# 501_RPiCM4.net
KiCad netlist of a schematic drawn in Altium Designer
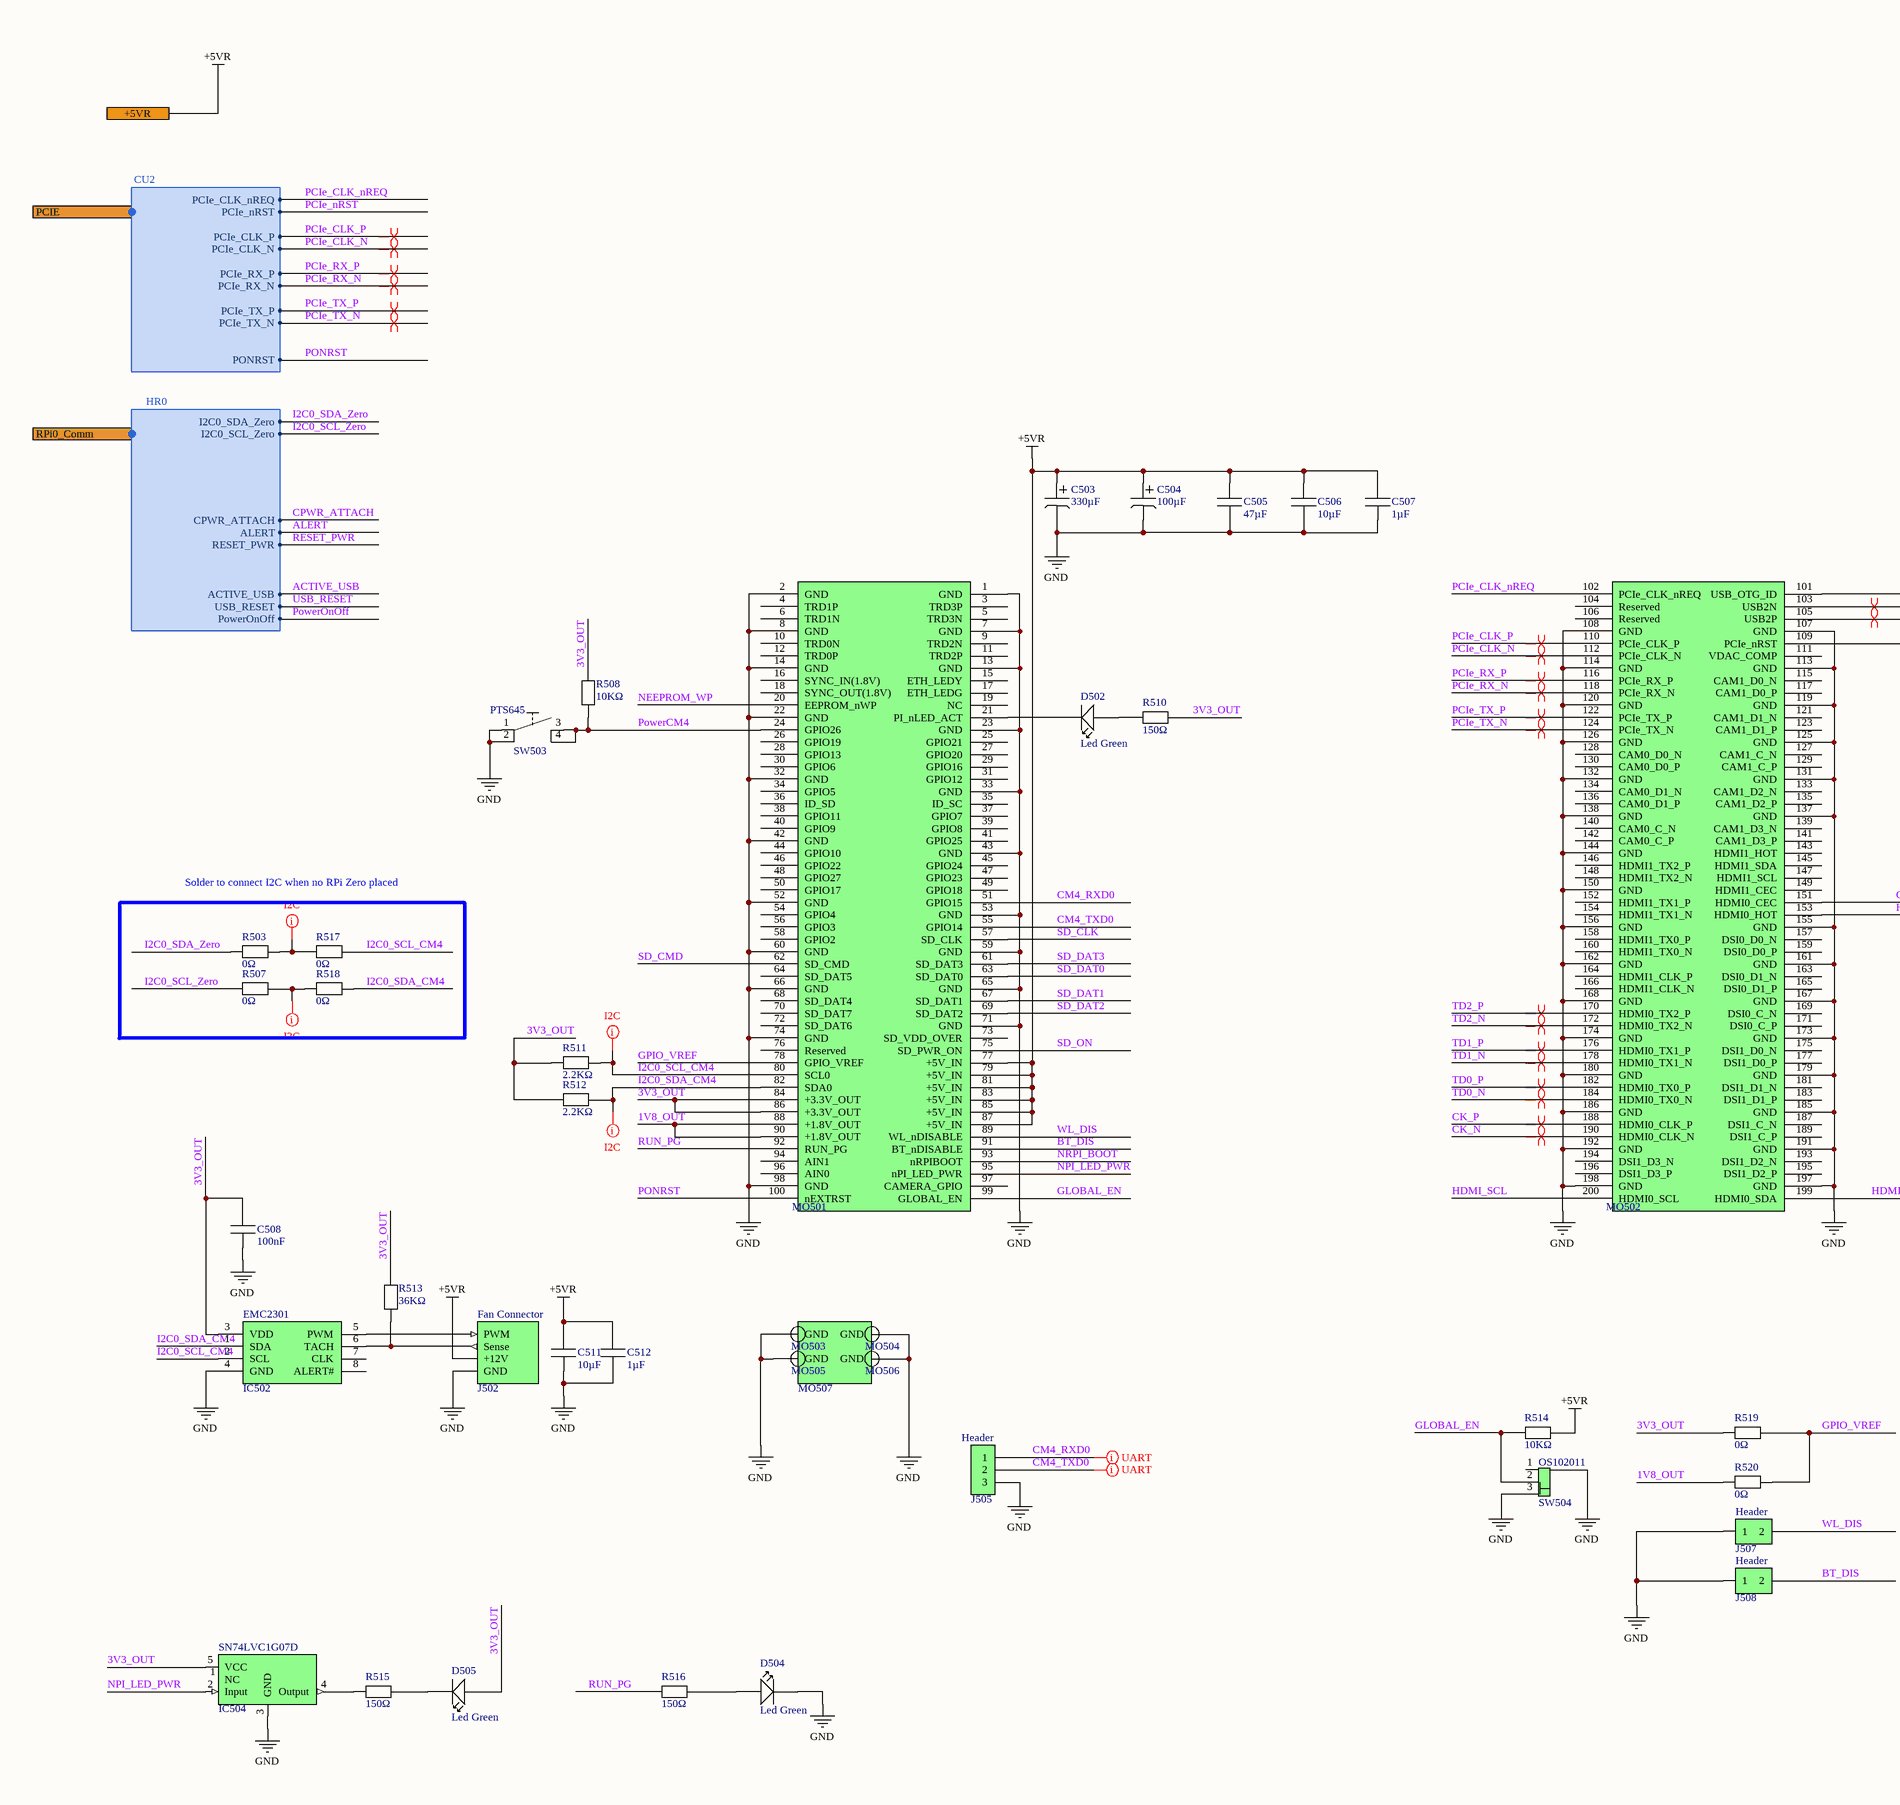
[diagram p0: 501_RPiCM4.SchDoc, left]
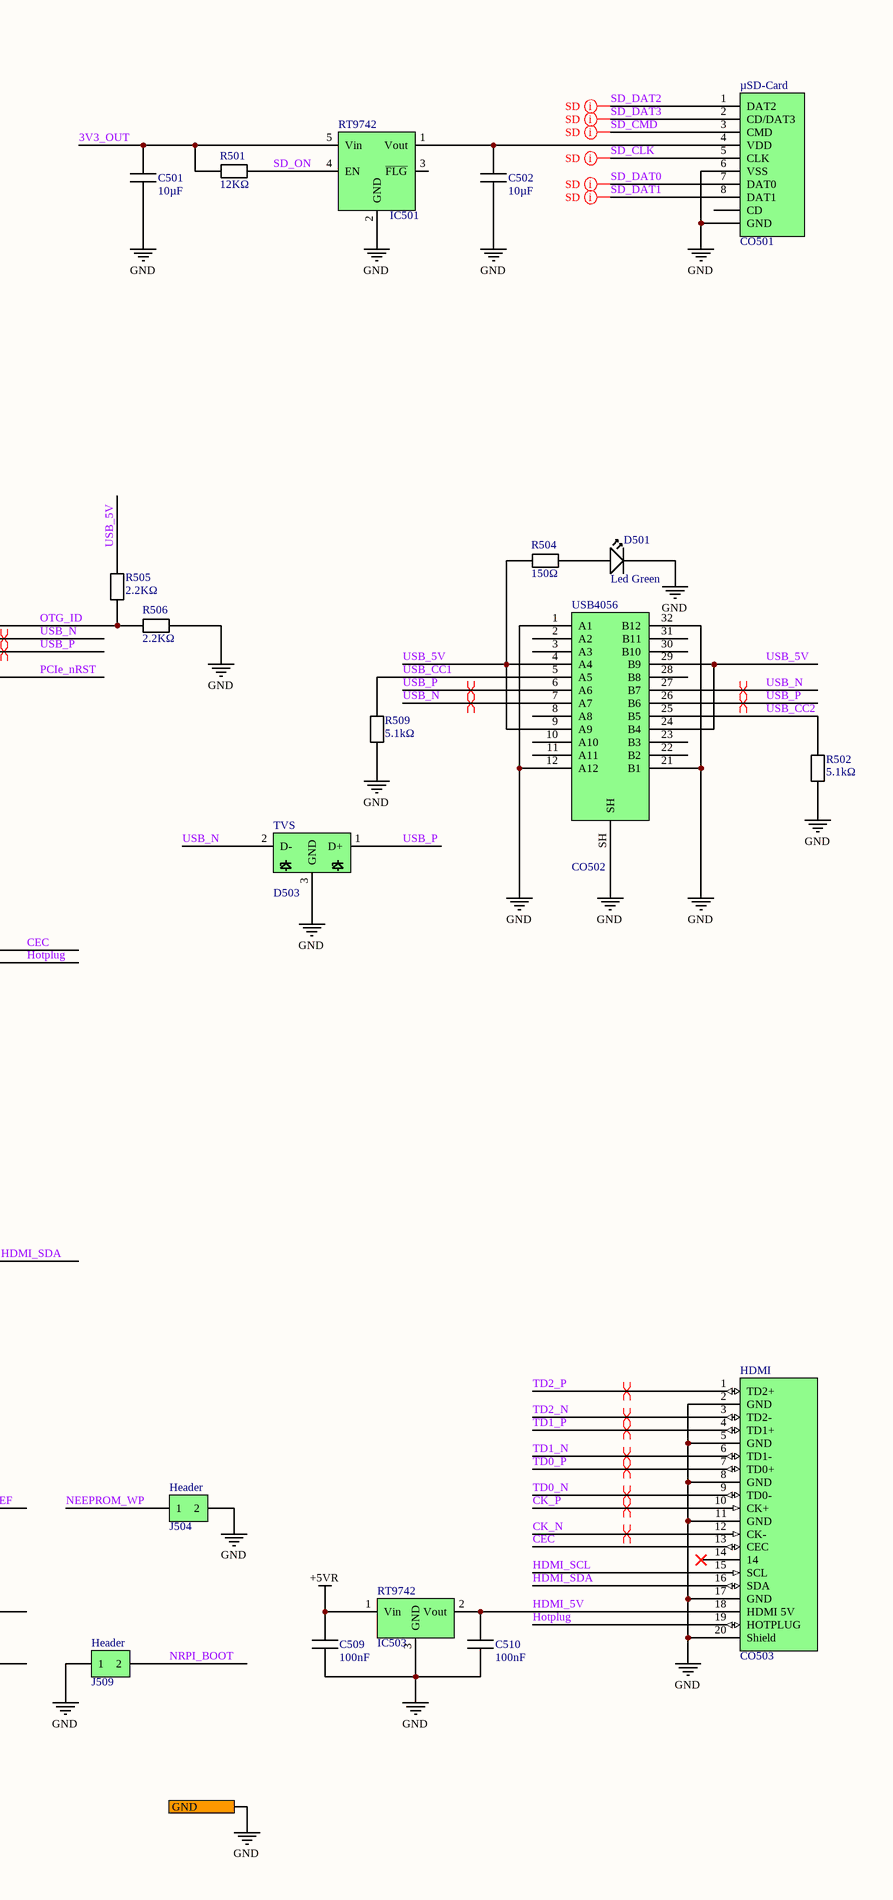
[diagram p1: 501_RPiCM4.SchDoc, right]

(export (version "E")
  (design (tool "Eeschema 10.0.6"))
  (components
    (comp (ref "C501")
      (value "10µF")
      (footprint "C0603")
      (description "10µF 16V 20% X5R")
      (fields
        (field (name "REFVAL") "10µF")
        (field (name "PART NUMBER") "CA0008")
        (field (name "MANFACTPART") "GRM188R61C106MAALD")
      )
      (libsource (lib "GTS_Database") (part "C"))
    )
    (comp (ref "C502")
      (value "10µF")
      (footprint "C0603")
      (description "10µF 16V 20% X5R")
      (fields
        (field (name "REFVAL") "10µF")
        (field (name "PART NUMBER") "CA0008")
        (field (name "MANFACTPART") "GRM188R61C106MAALD")
      )
      (libsource (lib "GTS_Database") (part "C"))
    )
    (comp (ref "C503")
      (value "330µF")
      (footprint "EC_E7")
      (description "330µF 16V 20% 16mΩ 4100mA")
      (fields
        (field (name "REFVAL") "330µF")
        (field (name "PART NUMBER") "CA0012")
        (field (name "MANFACTPART") "16SVPG330MX")
      )
      (libsource (lib "GTS_Database") (part "C+"))
    )
    (comp (ref "C504")
      (value "100µF")
      (footprint "EC_B6")
      (description "100µF 16V 20% 15mΩ 4000mA")
      (fields
        (field (name "REFVAL") "100µF")
        (field (name "PART NUMBER") "CA0011")
        (field (name "MANFACTPART") "16SVPG100M")
      )
      (libsource (lib "GTS_Database") (part "C+"))
    )
    (comp (ref "C505")
      (value "47µF")
      (footprint "C1210")
      (description "47µF 16V 20% X5R")
      (fields
        (field (name "REFVAL") "47µF")
        (field (name "PART NUMBER") "CA0007")
        (field (name "MANFACTPART") "EMK325ABJ476MM8P")
      )
      (libsource (lib "GTS_Database") (part "C"))
    )
    (comp (ref "C506")
      (value "10µF")
      (footprint "C0603")
      (description "10µF 16V 20% X5R")
      (fields
        (field (name "REFVAL") "10µF")
        (field (name "PART NUMBER") "CA0008")
        (field (name "MANFACTPART") "GRM188R61C106MAALD")
      )
      (libsource (lib "GTS_Database") (part "C"))
    )
    (comp (ref "C507")
      (value "1µF")
      (footprint "C0603")
      (description "1µF 16V 10% X5R")
      (fields
        (field (name "REFVAL") "1µF")
        (field (name "PART NUMBER") "CA0003")
        (field (name "MANFACTPART") "C1608X5R1C105K080AA")
      )
      (libsource (lib "GTS_Database") (part "C"))
    )
    (comp (ref "C508")
      (value "100nF")
      (footprint "C0402")
      (description "100nF 16V 10% X7R")
      (fields
        (field (name "REFVAL") "100nF")
        (field (name "PART NUMBER") "CA0010")
        (field (name "MANFACTPART") "GCM155R71C104KA55D")
      )
      (libsource (lib "GTS_Database") (part "C"))
    )
    (comp (ref "C509")
      (value "100nF")
      (footprint "C0402")
      (description "100nF 16V 10% X7R")
      (fields
        (field (name "REFVAL") "100nF")
        (field (name "PART NUMBER") "CA0010")
        (field (name "MANFACTPART") "GCM155R71C104KA55D")
      )
      (libsource (lib "GTS_Database") (part "C"))
    )
    (comp (ref "C510")
      (value "100nF")
      (footprint "C0402")
      (description "100nF 16V 10% X7R")
      (fields
        (field (name "REFVAL") "100nF")
        (field (name "PART NUMBER") "CA0010")
        (field (name "MANFACTPART") "GCM155R71C104KA55D")
      )
      (libsource (lib "GTS_Database") (part "C"))
    )
    (comp (ref "C511")
      (value "10µF")
      (footprint "C0603")
      (description "10µF 16V 20% X5R")
      (fields
        (field (name "REFVAL") "10µF")
        (field (name "PART NUMBER") "CA0008")
        (field (name "MANFACTPART") "GRM188R61C106MAALD")
      )
      (libsource (lib "GTS_Database") (part "C"))
    )
    (comp (ref "C512")
      (value "1µF")
      (footprint "C0603")
      (description "1µF 16V 10% X5R")
      (fields
        (field (name "REFVAL") "1µF")
        (field (name "PART NUMBER") "CA0003")
        (field (name "MANFACTPART") "C1608X5R1C105K080AA")
      )
      (libsource (lib "GTS_Database") (part "C"))
    )
    (comp (ref "CO501")
      (value "µSD-Card")
      (footprint "693071030811")
      (description "µSD-Card holder")
      (fields
        (field (name "REFVAL") "µSD-Card")
        (field (name "PART NUMBER") "CO0027")
        (field (name "MANFACTPART") "693071030811")
      )
      (libsource (lib "GTS_Database") (part "MICROSD-CARD"))
    )
    (comp (ref "CO502")
      (value "USB4056")
      (footprint "USB4056-03-A")
      (description "USB C connector Receptacle Horizontal")
      (fields
        (field (name "REFVAL") "USB4056")
        (field (name "PART NUMBER") "CO0030")
        (field (name "MANFACTPART") "USB4056-03-A")
      )
      (libsource (lib "GTS_Database") (part "USB-CC"))
    )
    (comp (ref "CO503")
      (value "HDMI")
      (footprint "HDMI")
      (fields
        (field (name "REFVAL") "HDMI")
        (field (name "PART NUMBER") "CO0007")
        (field (name "MANFACTPART") "10029449")
      )
      (libsource (lib "GTS_Database") (part "HDMI"))
    )
    (comp (ref "D501")
      (value "Led Green")
      (footprint "Led0805")
      (fields
        (field (name "REFVAL") "Led Green")
        (field (name "PART NUMBER") "DI0001")
        (field (name "MANFACTPART") "KP-2012CGCK")
      )
      (libsource (lib "GTS_Database") (part "Led"))
    )
    (comp (ref "D502")
      (value "Led Green")
      (footprint "Led0805")
      (fields
        (field (name "REFVAL") "Led Green")
        (field (name "PART NUMBER") "DI0001")
        (field (name "MANFACTPART") "KP-2012CGCK")
      )
      (libsource (lib "GTS_Database") (part "Led"))
    )
    (comp (ref "D503")
      (value "TVS")
      (footprint "SOT-3")
      (description "USB 2 TVS Diode")
      (fields
        (field (name "REFVAL") "TVS")
        (field (name "PART NUMBER") "DI0002")
        (field (name "MANFACTPART") "TPD2EUSB30DRTR")
      )
      (libsource (lib "GTS_Database") (part "USB2TVS"))
    )
    (comp (ref "D504")
      (value "Led Green")
      (footprint "Led0805")
      (fields
        (field (name "REFVAL") "Led Green")
        (field (name "PART NUMBER") "DI0001")
        (field (name "MANFACTPART") "KP-2012CGCK")
      )
      (libsource (lib "GTS_Database") (part "Led"))
    )
    (comp (ref "D505")
      (value "Led Green")
      (footprint "Led0805")
      (fields
        (field (name "REFVAL") "Led Green")
        (field (name "PART NUMBER") "DI0001")
        (field (name "MANFACTPART") "KP-2012CGCK")
      )
      (libsource (lib "GTS_Database") (part "Led"))
    )
    (comp (ref "IC501")
      (value "RT9742")
      (footprint "SOT-23-5")
      (description "RT9742 High side power switch")
      (fields
        (field (name "REFVAL") "RT9742")
        (field (name "PART NUMBER") "IC0029")
        (field (name "MANFACTPART") "RT9742GGJ5")
      )
      (libsource (lib "GTS_Database") (part "RT9742_EN"))
    )
    (comp (ref "IC502")
      (value "EMC2301")
      (footprint "MSOP-8_3X3")
      (description "Board Mount Temperature Sensors Single RPB-Based PWM Fan Speed CNTRL")
      (fields
        (field (name "REFVAL") "EMC2301")
        (field (name "PART NUMBER") "IC0054")
        (field (name "MANFACTPART") "EMC2301-1-ACZL-TR")
      )
      (libsource (lib "GTS_Database") (part "EMC2301"))
    )
    (comp (ref "IC503")
      (value "RT9742")
      (footprint "SOT-23")
      (description "RT9742SNGV")
      (fields (field (name "REFVAL") "RT9742") (field (name "PART NUMBER") "IC0011"))
      (libsource (lib "GTS_Database") (part "RT9742"))
    )
    (comp (ref "IC504")
      (value "SN74LVC1G07D")
      (footprint "SOT-23-5")
      (description "Buffer IC")
      (fields
        (field (name "REFVAL") "SN74LVC1G07D")
        (field (name "PART NUMBER") "IC0009")
        (field (name "MANFACTPART") "SN74LVC1G07DBVT")
      )
      (libsource (lib "GTS_Database") (part "SN74LVC1G07D"))
    )
    (comp (ref "J502")
      (value "Fan Connector")
      (footprint "470531000")
      (description "Fan Connector 4pin")
      (fields
        (field (name "REFVAL") "Fan Connector")
        (field (name "PART NUMBER") "CO0010")
        (field (name "MANFACTPART") "470531000")
      )
      (libsource (lib "GTS_Database") (part "FAN4P"))
    )
    (comp (ref "J504")
      (value "Header")
      (footprint "1X2P_2.54mm")
      (description "Header 1x2P")
      (fields
        (field (name "REFVAL") "Header")
        (field (name "PART NUMBER") "CO0012")
        (field (name "MANFACTPART") "G800W306018EU")
      )
      (libsource (lib "GTS_Database") (part "CONN1X2P"))
    )
    (comp (ref "J505")
      (value "Header")
      (footprint "1X3P_2.54mm")
      (description "Header 1x3P")
      (fields
        (field (name "REFVAL") "Header")
        (field (name "PART NUMBER") "CO0018")
        (field (name "MANFACTPART") "G800W305018EU")
      )
      (libsource (lib "GTS_Database") (part "CONN1X3P"))
    )
    (comp (ref "J507")
      (value "Header")
      (footprint "1X2P_2.54mm")
      (description "Header 1x2P")
      (fields
        (field (name "REFVAL") "Header")
        (field (name "PART NUMBER") "CO0012")
        (field (name "MANFACTPART") "G800W306018EU")
      )
      (libsource (lib "GTS_Database") (part "CONN1X2P"))
    )
    (comp (ref "J508")
      (value "Header")
      (footprint "1X2P_2.54mm")
      (description "Header 1x2P")
      (fields
        (field (name "REFVAL") "Header")
        (field (name "PART NUMBER") "CO0012")
        (field (name "MANFACTPART") "G800W306018EU")
      )
      (libsource (lib "GTS_Database") (part "CONN1X2P"))
    )
    (comp (ref "J509")
      (value "Header")
      (footprint "1X2P_2.54mm")
      (description "Header 1x2P")
      (fields
        (field (name "REFVAL") "Header")
        (field (name "PART NUMBER") "CO0012")
        (field (name "MANFACTPART") "G800W306018EU")
      )
      (libsource (lib "GTS_Database") (part "CONN1X2P"))
    )
    (comp (ref "MO501")
      (value "CM4-1")
      (footprint "CM4_001-100")
      (description "RPI CM4 Pin 1-100")
      (fields (field (name "PART NUMBER") "MO0012") (field (name "MANFACTPART") "DF40HC(3.0)-100DS-0.4V"))
      (libsource (lib "GTS_Database") (part "RPICM4_PART1"))
    )
    (comp (ref "MO502")
      (value "CM4-2")
      (footprint "CM4_101-200")
      (description "RPI CM4 Pin 101-200")
      (fields (field (name "PART NUMBER") "MO0013") (field (name "MANFACTPART") "DF40HC(3.0)-100DS-0.4V"))
      (libsource (lib "GTS_Database") (part "RPICM4_PART2"))
    )
    (comp (ref "MO503")
      (value "CM4-M")
      (footprint "CM4-M")
      (description "RPI CM4 Mounting Studs")
      (fields (field (name "PART NUMBER") "MO0014") (field (name "MANFACTPART") "9774030151R"))
      (libsource (lib "GTS_Database") (part "RPICM4_Mounting"))
    )
    (comp (ref "MO504")
      (value "CM4-M")
      (footprint "CM4-M")
      (description "RPI CM4 Mounting Studs")
      (fields (field (name "PART NUMBER") "MO0014") (field (name "MANFACTPART") "9774030151R"))
      (libsource (lib "GTS_Database") (part "RPICM4_Mounting"))
    )
    (comp (ref "MO505")
      (value "CM4-M")
      (footprint "CM4-M")
      (description "RPI CM4 Mounting Studs")
      (fields (field (name "PART NUMBER") "MO0014") (field (name "MANFACTPART") "9774030151R"))
      (libsource (lib "GTS_Database") (part "RPICM4_Mounting"))
    )
    (comp (ref "MO506")
      (value "CM4-M")
      (footprint "CM4-M")
      (description "RPI CM4 Mounting Studs")
      (fields (field (name "PART NUMBER") "MO0014") (field (name "MANFACTPART") "9774030151R"))
      (libsource (lib "GTS_Database") (part "RPICM4_Mounting"))
    )
    (comp (ref "MO507")
      (value "CM4")
      (footprint "RPICM4_Layout")
      (description "Outline of CM4")
      (fields (field (name "PART NUMBER") "MO0011") (field (name "MANFACTPART") "RPI CM4"))
      (libsource (lib "GTS_Database") (part "RPICM4_Layout"))
    )
    (comp (ref "R501")
      (value "12KΩ")
      (footprint "R0402")
      (description "12KΩ 1% 62.5mW")
      (fields
        (field (name "REFVAL") "12KΩ")
        (field (name "PART NUMBER") "RS0015")
        (field (name "MANFACTPART") "RC0402FR-1312KL")
      )
      (libsource (lib "GTS_Database") (part "R"))
    )
    (comp (ref "R502")
      (value "5.1kΩ")
      (footprint "R0402")
      (description "5.1KΩ 1% 62.5mW 100PPM")
      (fields
        (field (name "REFVAL") "5.1kΩ")
        (field (name "PART NUMBER") "RS0038")
        (field (name "MANFACTPART") "CRCW04025K10FKEDC")
      )
      (libsource (lib "GTS_Database") (part "R"))
    )
    (comp (ref "R503")
      (value "0Ω")
      (footprint "R0402")
      (description "0Ω 62.5mW")
      (fields
        (field (name "REFVAL") "0Ω")
        (field (name "PART NUMBER") "RS0074")
        (field (name "MANFACTPART") "0402WGJ0000TCE")
      )
      (libsource (lib "GTS_Database") (part "R"))
    )
    (comp (ref "R504")
      (value "150Ω")
      (footprint "R0603")
      (description "150Ω 1% 100mW")
      (fields
        (field (name "REFVAL") "150Ω")
        (field (name "PART NUMBER") "RS0001")
        (field (name "MANFACTPART") "MCWR06X1500FTL")
      )
      (libsource (lib "GTS_Database") (part "R"))
    )
    (comp (ref "R505")
      (value "2.2KΩ")
      (footprint "R0402")
      (description "2.2KΩ 5% 62.5mW")
      (fields
        (field (name "REFVAL") "2.2KΩ")
        (field (name "PART NUMBER") "RS0020")
        (field (name "MANFACTPART") "MCMR04X222 JTL")
      )
      (libsource (lib "GTS_Database") (part "R"))
    )
    (comp (ref "R506")
      (value "2.2KΩ")
      (footprint "R0402")
      (description "2.2KΩ 5% 62.5mW")
      (fields
        (field (name "REFVAL") "2.2KΩ")
        (field (name "PART NUMBER") "RS0020")
        (field (name "MANFACTPART") "MCMR04X222 JTL")
      )
      (libsource (lib "GTS_Database") (part "R"))
    )
    (comp (ref "R507")
      (value "0Ω")
      (footprint "R0402")
      (description "0Ω 62.5mW")
      (fields
        (field (name "REFVAL") "0Ω")
        (field (name "PART NUMBER") "RS0074")
        (field (name "MANFACTPART") "0402WGJ0000TCE")
      )
      (libsource (lib "GTS_Database") (part "R"))
    )
    (comp (ref "R508")
      (value "10KΩ")
      (footprint "R0402")
      (description "10KΩ 1% 62.5mW")
      (fields
        (field (name "REFVAL") "10KΩ")
        (field (name "PART NUMBER") "RS0011")
        (field (name "MANFACTPART") "WR04X1002FTL")
      )
      (libsource (lib "GTS_Database") (part "R"))
    )
    (comp (ref "R509")
      (value "5.1kΩ")
      (footprint "R0402")
      (description "5.1KΩ 1% 62.5mW 100PPM")
      (fields
        (field (name "REFVAL") "5.1kΩ")
        (field (name "PART NUMBER") "RS0038")
        (field (name "MANFACTPART") "CRCW04025K10FKEDC")
      )
      (libsource (lib "GTS_Database") (part "R"))
    )
    (comp (ref "R510")
      (value "150Ω")
      (footprint "R0603")
      (description "150Ω 1% 100mW")
      (fields
        (field (name "REFVAL") "150Ω")
        (field (name "PART NUMBER") "RS0001")
        (field (name "MANFACTPART") "MCWR06X1500FTL")
      )
      (libsource (lib "GTS_Database") (part "R"))
    )
    (comp (ref "R511")
      (value "2.2KΩ")
      (footprint "R0402")
      (description "2.2KΩ 5% 62.5mW")
      (fields
        (field (name "REFVAL") "2.2KΩ")
        (field (name "PART NUMBER") "RS0020")
        (field (name "MANFACTPART") "MCMR04X222 JTL")
      )
      (libsource (lib "GTS_Database") (part "R"))
    )
    (comp (ref "R512")
      (value "2.2KΩ")
      (footprint "R0402")
      (description "2.2KΩ 5% 62.5mW")
      (fields
        (field (name "REFVAL") "2.2KΩ")
        (field (name "PART NUMBER") "RS0020")
        (field (name "MANFACTPART") "MCMR04X222 JTL")
      )
      (libsource (lib "GTS_Database") (part "R"))
    )
    (comp (ref "R513")
      (value "36KΩ")
      (footprint "R0402")
      (description "36KΩ 1% 62.5mW 100PPM")
      (fields
        (field (name "REFVAL") "36KΩ")
        (field (name "PART NUMBER") "RS0051")
        (field (name "MANFACTPART") "ERJ-2RKF3602X")
      )
      (libsource (lib "GTS_Database") (part "R"))
    )
    (comp (ref "R514")
      (value "10KΩ")
      (footprint "R0603")
      (description "10KΩ 5% 100mW")
      (fields
        (field (name "REFVAL") "10KΩ")
        (field (name "PART NUMBER") "RS0003")
        (field (name "MANFACTPART") "WR06X103 JTL")
      )
      (libsource (lib "GTS_Database") (part "R"))
    )
    (comp (ref "R515")
      (value "150Ω")
      (footprint "R0603")
      (description "150Ω 1% 100mW")
      (fields
        (field (name "REFVAL") "150Ω")
        (field (name "PART NUMBER") "RS0001")
        (field (name "MANFACTPART") "MCWR06X1500FTL")
      )
      (libsource (lib "GTS_Database") (part "R"))
    )
    (comp (ref "R516")
      (value "150Ω")
      (footprint "R0603")
      (description "150Ω 1% 100mW")
      (fields
        (field (name "REFVAL") "150Ω")
        (field (name "PART NUMBER") "RS0001")
        (field (name "MANFACTPART") "MCWR06X1500FTL")
      )
      (libsource (lib "GTS_Database") (part "R"))
    )
    (comp (ref "R517")
      (value "0Ω")
      (footprint "R0402")
      (description "0Ω 62.5mW")
      (fields
        (field (name "REFVAL") "0Ω")
        (field (name "PART NUMBER") "RS0074")
        (field (name "MANFACTPART") "0402WGJ0000TCE")
      )
      (libsource (lib "GTS_Database") (part "R"))
    )
    (comp (ref "R518")
      (value "0Ω")
      (footprint "R0402")
      (description "0Ω 62.5mW")
      (fields
        (field (name "REFVAL") "0Ω")
        (field (name "PART NUMBER") "RS0074")
        (field (name "MANFACTPART") "0402WGJ0000TCE")
      )
      (libsource (lib "GTS_Database") (part "R"))
    )
    (comp (ref "R519")
      (value "0Ω")
      (footprint "R0402")
      (description "0Ω 62.5mW")
      (fields
        (field (name "REFVAL") "0Ω")
        (field (name "PART NUMBER") "RS0074")
        (field (name "MANFACTPART") "0402WGJ0000TCE")
      )
      (libsource (lib "GTS_Database") (part "R"))
    )
    (comp (ref "R520")
      (value "0Ω")
      (footprint "R0402")
      (description "0Ω 62.5mW")
      (fields
        (field (name "REFVAL") "0Ω")
        (field (name "PART NUMBER") "RS0074")
        (field (name "MANFACTPART") "0402WGJ0000TCE")
      )
      (libsource (lib "GTS_Database") (part "R"))
    )
    (comp (ref "SW503")
      (value "PTS645")
      (footprint "PTS645-V")
      (description "TACTILE SWITCH SPST")
      (fields
        (field (name "REFVAL") "PTS645")
        (field (name "PART NUMBER") "SW0003")
        (field (name "MANFACTPART") "PTS645VK832LFS")
      )
      (libsource (lib "GTS_Database") (part "SPST-2-4"))
    )
    (comp (ref "SW504")
      (value "OS102011")
      (footprint "OS10_Series")
      (description "Miniature Slide Switch SPDT")
      (fields
        (field (name "REFVAL") "OS102011")
        (field (name "PART NUMBER") "SW0001")
        (field (name "MANFACTPART") "OS102011MS2QN1")
      )
      (libsource (lib "GTS_Database") (part "SPDT"))
    )
  )
  (nets
    (net (code "3") (name "+5VR") (class "Default")
      (node (ref "C503") (pin "1") (pinfunction "1_1") (pintype "passive"))
      (node (ref "C504") (pin "1") (pinfunction "1_1") (pintype "passive"))
      (node (ref "C505") (pin "1") (pinfunction "1_1") (pintype "passive"))
      (node (ref "C506") (pin "1") (pinfunction "1_1") (pintype "passive"))
      (node (ref "C507") (pin "1") (pinfunction "1_1") (pintype "passive"))
      (node (ref "C509") (pin "1") (pinfunction "1_1") (pintype "passive"))
      (node (ref "C511") (pin "1") (pinfunction "1_1") (pintype "passive"))
      (node (ref "C512") (pin "1") (pinfunction "1_1") (pintype "passive"))
      (node (ref "IC503") (pin "1") (pinfunction "Vin_1") (pintype "power_in"))
      (node (ref "J502") (pin "3") (pinfunction "+12V_3") (pintype "power_in"))
      (node (ref "MO501") (pin "77") (pinfunction "+5V_IN_77") (pintype "passive"))
      (node (ref "MO501") (pin "79") (pinfunction "+5V_IN_79") (pintype "passive"))
      (node (ref "MO501") (pin "81") (pinfunction "+5V_IN_81") (pintype "passive"))
      (node (ref "MO501") (pin "83") (pinfunction "+5V_IN_83") (pintype "passive"))
      (node (ref "MO501") (pin "85") (pinfunction "+5V_IN_85") (pintype "passive"))
      (node (ref "MO501") (pin "87") (pinfunction "+5V_IN_87") (pintype "passive"))
      (node (ref "R514") (pin "2") (pinfunction "2_2") (pintype "passive"))
    )
    (net (code "4") (name "/1V8_OUT") (class "Default")
      (node (ref "MO501") (pin "88") (pinfunction "+1.8V_OUT_88") (pintype "passive"))
      (node (ref "MO501") (pin "90") (pinfunction "+1.8V_OUT_90") (pintype "passive"))
      (node (ref "R520") (pin "1") (pinfunction "1_1") (pintype "passive"))
    )
    (net (code "5") (name "/3V3_OUT") (class "Default")
      (node (ref "C501") (pin "1") (pinfunction "1_1") (pintype "passive"))
      (node (ref "C508") (pin "1") (pinfunction "1_1") (pintype "passive"))
      (node (ref "D505") (pin "A") (pinfunction "A_A") (pintype "passive"))
      (node (ref "IC501") (pin "5") (pinfunction "Vin_5") (pintype "power_in"))
      (node (ref "IC502") (pin "3") (pinfunction "VDD_3") (pintype "passive"))
      (node (ref "IC504") (pin "5") (pinfunction "VCC_5") (pintype "power_in"))
      (node (ref "MO501") (pin "84") (pinfunction "+3.3V_OUT_84") (pintype "passive"))
      (node (ref "MO501") (pin "86") (pinfunction "+3.3V_OUT_86") (pintype "passive"))
      (node (ref "R501") (pin "1") (pinfunction "1_1") (pintype "passive"))
      (node (ref "R508") (pin "2") (pinfunction "2_2") (pintype "passive"))
      (node (ref "R510") (pin "2") (pinfunction "2_2") (pintype "passive"))
      (node (ref "R511") (pin "1") (pinfunction "1_1") (pintype "passive"))
      (node (ref "R512") (pin "1") (pinfunction "1_1") (pintype "passive"))
      (node (ref "R513") (pin "2") (pinfunction "2_2") (pintype "passive"))
      (node (ref "R519") (pin "1") (pinfunction "1_1") (pintype "passive"))
    )
    (net (code "8") (name "/BT_DIS") (class "Default")
      (node (ref "J508") (pin "2") (pinfunction "2_2") (pintype "passive"))
      (node (ref "MO501") (pin "91") (pinfunction "BT_nDISABLE_91") (pintype "passive"))
    )
    (net (code "9") (name "/CEC") (class "Default")
      (node (ref "CO503") (pin "13") (pinfunction "CEC_13") (pintype "bidirectional"))
      (node (ref "MO502") (pin "151") (pinfunction "HDMI0_CEC_151") (pintype "passive"))
    )
    (net (code "10") (name "/CK_N") (class "Default")
      (node (ref "CO503") (pin "12") (pinfunction "CK-_12") (pintype "input"))
      (node (ref "MO502") (pin "190") (pinfunction "HDMI0_CLK_N_190") (pintype "passive"))
    )
    (net (code "11") (name "/CK_P") (class "Default")
      (node (ref "CO503") (pin "10") (pinfunction "CK+_10") (pintype "input"))
      (node (ref "MO502") (pin "188") (pinfunction "HDMI0_CLK_P_188") (pintype "passive"))
    )
    (net (code "12") (name "/CM4_RXD0") (class "Default")
      (node (ref "J505") (pin "1") (pinfunction "1_1") (pintype "passive"))
      (node (ref "MO501") (pin "51") (pinfunction "GPIO15_51") (pintype "passive"))
    )
    (net (code "13") (name "/CM4_TXD0") (class "Default")
      (node (ref "J505") (pin "2") (pinfunction "2_2") (pintype "passive"))
      (node (ref "MO501") (pin "55") (pinfunction "GPIO14_55") (pintype "passive"))
    )
    (net (code "15") (name "/GLOBAL_EN") (class "Default")
      (node (ref "MO501") (pin "99") (pinfunction "GLOBAL_EN_99") (pintype "passive"))
      (node (ref "R514") (pin "1") (pinfunction "1_1") (pintype "passive"))
      (node (ref "SW504") (pin "2") (pinfunction "2_2") (pintype "passive"))
    )
    (net (code "16") (name "/GPIO_VREF") (class "Default")
      (node (ref "MO501") (pin "78") (pinfunction "GPIO_VREF_78") (pintype "passive"))
      (node (ref "R519") (pin "2") (pinfunction "2_2") (pintype "passive"))
      (node (ref "R520") (pin "2") (pinfunction "2_2") (pintype "passive"))
    )
    (net (code "17") (name "/HDMI_5V") (class "Default")
      (node (ref "C510") (pin "1") (pinfunction "1_1") (pintype "passive"))
      (node (ref "CO503") (pin "18") (pinfunction "HDMI_5V_18") (pintype "power_in"))
      (node (ref "IC503") (pin "2") (pinfunction "Vout_2") (pintype "power_in"))
    )
    (net (code "18") (name "/HDMI_SCL") (class "Default")
      (node (ref "CO503") (pin "15") (pinfunction "SCL_15") (pintype "input"))
      (node (ref "MO502") (pin "200") (pinfunction "HDMI0_SCL_200") (pintype "passive"))
    )
    (net (code "19") (name "/HDMI_SDA") (class "Default")
      (node (ref "CO503") (pin "16") (pinfunction "SDA_16") (pintype "bidirectional"))
      (node (ref "MO502") (pin "199") (pinfunction "HDMI0_SDA_199") (pintype "passive"))
    )
    (net (code "20") (name "/Hotplug") (class "Default")
      (node (ref "CO503") (pin "19") (pinfunction "HOTPLUG_19") (pintype "bidirectional"))
      (node (ref "MO502") (pin "153") (pinfunction "HDMI0_HOT_153") (pintype "passive"))
    )
    (net (code "21") (name "/I2C0_SCL_CM4") (class "Default")
      (node (ref "IC502") (pin "2") (pinfunction "SCL_2") (pintype "passive"))
      (node (ref "MO501") (pin "80") (pinfunction "SCL0_80") (pintype "passive"))
      (node (ref "R511") (pin "2") (pinfunction "2_2") (pintype "passive"))
      (node (ref "R517") (pin "2") (pinfunction "2_2") (pintype "passive"))
    )
    (net (code "22") (name "/I2C0_SCL_Zero") (class "Default")
      (node (ref "R507") (pin "1") (pinfunction "1_1") (pintype "passive"))
    )
    (net (code "23") (name "/I2C0_SDA_CM4") (class "Default")
      (node (ref "IC502") (pin "1") (pinfunction "SDA_1") (pintype "passive"))
      (node (ref "MO501") (pin "82") (pinfunction "SDA0_82") (pintype "passive"))
      (node (ref "R512") (pin "2") (pinfunction "2_2") (pintype "passive"))
      (node (ref "R518") (pin "2") (pinfunction "2_2") (pintype "passive"))
    )
    (net (code "24") (name "/I2C0_SDA_Zero") (class "Default")
      (node (ref "R503") (pin "1") (pinfunction "1_1") (pintype "passive"))
    )
    (net (code "25") (name "/NEEPROM_WP") (class "Default")
      (node (ref "J504") (pin "1") (pinfunction "1_1") (pintype "passive"))
      (node (ref "MO501") (pin "20") (pinfunction "EEPROM_nWP_20") (pintype "passive"))
    )
    (net (code "26") (name "/NPI_LED_PWR") (class "Default")
      (node (ref "IC504") (pin "2") (pinfunction "Input_2") (pintype "input"))
      (node (ref "MO501") (pin "95") (pinfunction "nPI_LED_PWR_95") (pintype "passive"))
    )
    (net (code "27") (name "/NRPI_BOOT") (class "Default")
      (node (ref "J509") (pin "2") (pinfunction "2_2") (pintype "passive"))
      (node (ref "MO501") (pin "93") (pinfunction "nRPIBOOT_93") (pintype "passive"))
    )
    (net (code "28") (name "/OTG_ID") (class "Default")
      (node (ref "MO502") (pin "101") (pinfunction "USB_OTG_ID_101") (pintype "passive"))
      (node (ref "R505") (pin "1") (pinfunction "1_1") (pintype "passive"))
      (node (ref "R506") (pin "2") (pinfunction "2_2") (pintype "passive"))
    )
    (net (code "29") (name "/PCIe_CLK_N") (class "Default")
      (node (ref "MO502") (pin "112") (pinfunction "PCIe_CLK_N_112") (pintype "passive"))
    )
    (net (code "30") (name "/PCIe_CLK_P") (class "Default")
      (node (ref "MO502") (pin "110") (pinfunction "PCIe_CLK_P_110") (pintype "passive"))
    )
    (net (code "31") (name "/PCIe_CLK_nREQ") (class "Default")
      (node (ref "MO502") (pin "102") (pinfunction "PCIe_CLK_nREQ_102") (pintype "passive"))
    )
    (net (code "32") (name "/PCIe_RX_N") (class "Default")
      (node (ref "MO502") (pin "118") (pinfunction "PCIe_RX_N_118") (pintype "passive"))
    )
    (net (code "33") (name "/PCIe_RX_P") (class "Default")
      (node (ref "MO502") (pin "116") (pinfunction "PCIe_RX_P_116") (pintype "passive"))
    )
    (net (code "34") (name "/PCIe_TX_N") (class "Default")
      (node (ref "MO502") (pin "124") (pinfunction "PCIe_TX_N_124") (pintype "passive"))
    )
    (net (code "35") (name "/PCIe_TX_P") (class "Default")
      (node (ref "MO502") (pin "122") (pinfunction "PCIe_TX_P_122") (pintype "passive"))
    )
    (net (code "36") (name "/PCIe_nRST") (class "Default")
      (node (ref "MO502") (pin "109") (pinfunction "PCIe_nRST_109") (pintype "passive"))
    )
    (net (code "37") (name "/PONRST") (class "Default")
      (node (ref "MO501") (pin "100") (pinfunction "nEXTRST_100") (pintype "passive"))
    )
    (net (code "38") (name "/PowerCM4") (class "Default")
      (node (ref "MO501") (pin "24") (pinfunction "GPIO26_24") (pintype "passive"))
      (node (ref "R508") (pin "1") (pinfunction "1_1") (pintype "passive"))
      (node (ref "SW503") (pin "3") (pinfunction "3_3") (pintype "passive"))
      (node (ref "SW503") (pin "4") (pinfunction "4_4") (pintype "passive"))
    )
    (net (code "41") (name "/RUN_PG") (class "Default")
      (node (ref "MO501") (pin "92") (pinfunction "RUN_PG_92") (pintype "passive"))
      (node (ref "R516") (pin "1") (pinfunction "1_1") (pintype "passive"))
    )
    (net (code "42") (name "/SD_CLK") (class "Default")
      (node (ref "CO501") (pin "5") (pinfunction "CLK_5") (pintype "passive"))
      (node (ref "MO501") (pin "57") (pinfunction "SD_CLK_57") (pintype "passive"))
    )
    (net (code "43") (name "/SD_CMD") (class "Default")
      (node (ref "CO501") (pin "3") (pinfunction "CMD_3") (pintype "passive"))
      (node (ref "MO501") (pin "62") (pinfunction "SD_CMD_62") (pintype "passive"))
    )
    (net (code "44") (name "/SD_DAT0") (class "Default")
      (node (ref "CO501") (pin "7") (pinfunction "DAT0_7") (pintype "passive"))
      (node (ref "MO501") (pin "63") (pinfunction "SD_DAT0_63") (pintype "passive"))
    )
    (net (code "45") (name "/SD_DAT1") (class "Default")
      (node (ref "CO501") (pin "8") (pinfunction "DAT1_8") (pintype "passive"))
      (node (ref "MO501") (pin "67") (pinfunction "SD_DAT1_67") (pintype "passive"))
    )
    (net (code "46") (name "/SD_DAT2") (class "Default")
      (node (ref "CO501") (pin "1") (pinfunction "DAT2_1") (pintype "passive"))
      (node (ref "MO501") (pin "69") (pinfunction "SD_DAT2_69") (pintype "passive"))
    )
    (net (code "47") (name "/SD_DAT3") (class "Default")
      (node (ref "CO501") (pin "2") (pinfunction "CD/DAT3_2") (pintype "passive"))
      (node (ref "MO501") (pin "61") (pinfunction "SD_DAT3_61") (pintype "passive"))
    )
    (net (code "48") (name "/SD_ON") (class "Default")
      (node (ref "IC501") (pin "4") (pinfunction "EN_4") (pintype "power_in"))
      (node (ref "MO501") (pin "75") (pinfunction "SD_PWR_ON_75") (pintype "passive"))
      (node (ref "R501") (pin "2") (pinfunction "2_2") (pintype "passive"))
    )
    (net (code "49") (name "/TD0_N") (class "Default")
      (node (ref "CO503") (pin "9") (pinfunction "TD0-_9") (pintype "bidirectional"))
      (node (ref "MO502") (pin "184") (pinfunction "HDMI0_TX0_N_184") (pintype "passive"))
    )
    (net (code "50") (name "/TD0_P") (class "Default")
      (node (ref "CO503") (pin "7") (pinfunction "TD0+_7") (pintype "bidirectional"))
      (node (ref "MO502") (pin "182") (pinfunction "HDMI0_TX0_P_182") (pintype "passive"))
    )
    (net (code "51") (name "/TD1_N") (class "Default")
      (node (ref "CO503") (pin "6") (pinfunction "TD1-_6") (pintype "bidirectional"))
      (node (ref "MO502") (pin "178") (pinfunction "HDMI0_TX1_N_178") (pintype "passive"))
    )
    (net (code "52") (name "/TD1_P") (class "Default")
      (node (ref "CO503") (pin "4") (pinfunction "TD1+_4") (pintype "bidirectional"))
      (node (ref "MO502") (pin "176") (pinfunction "HDMI0_TX1_P_176") (pintype "passive"))
    )
    (net (code "53") (name "/TD2_N") (class "Default")
      (node (ref "CO503") (pin "3") (pinfunction "TD2-_3") (pintype "bidirectional"))
      (node (ref "MO502") (pin "172") (pinfunction "HDMI0_TX2_N_172") (pintype "passive"))
    )
    (net (code "54") (name "/TD2_P") (class "Default")
      (node (ref "CO503") (pin "1") (pinfunction "TD2+_1") (pintype "bidirectional"))
      (node (ref "MO502") (pin "170") (pinfunction "HDMI0_TX2_P_170") (pintype "passive"))
    )
    (net (code "55") (name "/USB_5V") (class "Default")
      (node (ref "CO502") (pin "24") (pinfunction "B4_24") (pintype "passive"))
      (node (ref "CO502") (pin "29") (pinfunction "B9_29") (pintype "passive"))
      (node (ref "CO502") (pin "4") (pinfunction "A4_4") (pintype "passive"))
      (node (ref "CO502") (pin "9") (pinfunction "A9_9") (pintype "passive"))
      (node (ref "R504") (pin "1") (pinfunction "1_1") (pintype "passive"))
      (node (ref "R505") (pin "2") (pinfunction "2_2") (pintype "passive"))
    )
    (net (code "56") (name "/USB_CC1") (class "Default")
      (node (ref "CO502") (pin "5") (pinfunction "A5_5") (pintype "passive"))
      (node (ref "R509") (pin "2") (pinfunction "2_2") (pintype "passive"))
    )
    (net (code "57") (name "/USB_CC2") (class "Default")
      (node (ref "CO502") (pin "25") (pinfunction "B5_25") (pintype "passive"))
      (node (ref "R502") (pin "2") (pinfunction "2_2") (pintype "passive"))
    )
    (net (code "58") (name "/USB_N") (class "Default")
      (node (ref "CO502") (pin "27") (pinfunction "B7_27") (pintype "passive"))
      (node (ref "CO502") (pin "7") (pinfunction "A7_7") (pintype "passive"))
      (node (ref "D503") (pin "2") (pinfunction "D-_2") (pintype "passive"))
      (node (ref "MO502") (pin "103") (pinfunction "USB2N_103") (pintype "passive"))
    )
    (net (code "59") (name "/USB_P") (class "Default")
      (node (ref "CO502") (pin "26") (pinfunction "B6_26") (pintype "passive"))
      (node (ref "CO502") (pin "6") (pinfunction "A6_6") (pintype "passive"))
      (node (ref "D503") (pin "1") (pinfunction "D+_1") (pintype "passive"))
      (node (ref "MO502") (pin "105") (pinfunction "USB2P_105") (pintype "passive"))
    )
    (net (code "61") (name "/WL_DIS") (class "Default")
      (node (ref "J507") (pin "2") (pinfunction "2_2") (pintype "passive"))
      (node (ref "MO501") (pin "89") (pinfunction "WL_nDISABLE_89") (pintype "passive"))
    )
    (net (code "64") (name "GND") (class "Default")
      (node (ref "C501") (pin "2") (pinfunction "2_2") (pintype "passive"))
      (node (ref "C502") (pin "2") (pinfunction "2_2") (pintype "passive"))
      (node (ref "C503") (pin "2") (pinfunction "2_2") (pintype "passive"))
      (node (ref "C504") (pin "2") (pinfunction "2_2") (pintype "passive"))
      (node (ref "C505") (pin "2") (pinfunction "2_2") (pintype "passive"))
      (node (ref "C506") (pin "2") (pinfunction "2_2") (pintype "passive"))
      (node (ref "C507") (pin "2") (pinfunction "2_2") (pintype "passive"))
      (node (ref "C508") (pin "2") (pinfunction "2_2") (pintype "passive"))
      (node (ref "C509") (pin "2") (pinfunction "2_2") (pintype "passive"))
      (node (ref "C510") (pin "2") (pinfunction "2_2") (pintype "passive"))
      (node (ref "C511") (pin "2") (pinfunction "2_2") (pintype "passive"))
      (node (ref "C512") (pin "2") (pinfunction "2_2") (pintype "passive"))
      (node (ref "CO501") (pin "6") (pinfunction "VSS_6") (pintype "passive"))
      (node (ref "CO501") (pin "GND") (pinfunction "GND_GND") (pintype "passive"))
      (node (ref "CO502") (pin "1") (pinfunction "A1_1") (pintype "passive"))
      (node (ref "CO502") (pin "12") (pinfunction "A12_12") (pintype "passive"))
      (node (ref "CO502") (pin "21") (pinfunction "B1_21") (pintype "passive"))
      (node (ref "CO502") (pin "32") (pinfunction "B12_32") (pintype "passive"))
      (node (ref "CO502") (pin "SH") (pinfunction "SH_SH") (pintype "power_in"))
      (node (ref "CO503") (pin "11") (pinfunction "GND_11") (pintype "power_in"))
      (node (ref "CO503") (pin "17") (pinfunction "GND_17") (pintype "power_in"))
      (node (ref "CO503") (pin "2") (pinfunction "GND_2") (pintype "power_in"))
      (node (ref "CO503") (pin "20") (pinfunction "Shield_20") (pintype "power_in"))
      (node (ref "CO503") (pin "5") (pinfunction "GND_5") (pintype "power_in"))
      (node (ref "CO503") (pin "8") (pinfunction "GND_8") (pintype "power_in"))
      (node (ref "D501") (pin "K") (pinfunction "K_K") (pintype "passive"))
      (node (ref "D503") (pin "3") (pinfunction "GND_3") (pintype "power_in"))
      (node (ref "D504") (pin "K") (pinfunction "K_K") (pintype "passive"))
      (node (ref "IC501") (pin "2") (pinfunction "GND_2") (pintype "power_in"))
      (node (ref "IC502") (pin "4") (pinfunction "GND_4") (pintype "passive"))
      (node (ref "IC503") (pin "3") (pinfunction "GND_3") (pintype "power_in"))
      (node (ref "IC504") (pin "3") (pinfunction "GND_3") (pintype "power_in"))
      (node (ref "J502") (pin "4") (pinfunction "GND_4") (pintype "power_in"))
      (node (ref "J504") (pin "2") (pinfunction "2_2") (pintype "passive"))
      (node (ref "J505") (pin "3") (pinfunction "3_3") (pintype "passive"))
      (node (ref "J507") (pin "1") (pinfunction "1_1") (pintype "passive"))
      (node (ref "J508") (pin "1") (pinfunction "1_1") (pintype "passive"))
      (node (ref "J509") (pin "1") (pinfunction "1_1") (pintype "passive"))
      (node (ref "MO501") (pin "1") (pinfunction "GND_1") (pintype "passive"))
      (node (ref "MO501") (pin "13") (pinfunction "GND_13") (pintype "passive"))
      (node (ref "MO501") (pin "14") (pinfunction "GND_14") (pintype "passive"))
      (node (ref "MO501") (pin "2") (pinfunction "GND_2") (pintype "passive"))
      (node (ref "MO501") (pin "22") (pinfunction "GND_22") (pintype "passive"))
      (node (ref "MO501") (pin "23") (pinfunction "GND_23") (pintype "passive"))
      (node (ref "MO501") (pin "32") (pinfunction "GND_32") (pintype "passive"))
      (node (ref "MO501") (pin "33") (pinfunction "GND_33") (pintype "passive"))
      (node (ref "MO501") (pin "42") (pinfunction "GND_42") (pintype "passive"))
      (node (ref "MO501") (pin "43") (pinfunction "GND_43") (pintype "passive"))
      (node (ref "MO501") (pin "52") (pinfunction "GND_52") (pintype "passive"))
      (node (ref "MO501") (pin "53") (pinfunction "GND_53") (pintype "passive"))
      (node (ref "MO501") (pin "59") (pinfunction "GND_59") (pintype "passive"))
      (node (ref "MO501") (pin "60") (pinfunction "GND_60") (pintype "passive"))
      (node (ref "MO501") (pin "65") (pinfunction "GND_65") (pintype "passive"))
      (node (ref "MO501") (pin "66") (pinfunction "GND_66") (pintype "passive"))
      (node (ref "MO501") (pin "7") (pinfunction "GND_7") (pintype "passive"))
      (node (ref "MO501") (pin "71") (pinfunction "GND_71") (pintype "passive"))
      (node (ref "MO501") (pin "74") (pinfunction "GND_74") (pintype "passive"))
      (node (ref "MO501") (pin "8") (pinfunction "GND_8") (pintype "passive"))
      (node (ref "MO501") (pin "98") (pinfunction "GND_98") (pintype "passive"))
      (node (ref "MO502") (pin "107") (pinfunction "GND_107") (pintype "passive"))
      (node (ref "MO502") (pin "108") (pinfunction "GND_108") (pintype "passive"))
      (node (ref "MO502") (pin "113") (pinfunction "GND_113") (pintype "passive"))
      (node (ref "MO502") (pin "114") (pinfunction "GND_114") (pintype "passive"))
      (node (ref "MO502") (pin "119") (pinfunction "GND_119") (pintype "passive"))
      (node (ref "MO502") (pin "120") (pinfunction "GND_120") (pintype "passive"))
      (node (ref "MO502") (pin "125") (pinfunction "GND_125") (pintype "passive"))
      (node (ref "MO502") (pin "126") (pinfunction "GND_126") (pintype "passive"))
      (node (ref "MO502") (pin "131") (pinfunction "GND_131") (pintype "passive"))
      (node (ref "MO502") (pin "132") (pinfunction "GND_132") (pintype "passive"))
      (node (ref "MO502") (pin "137") (pinfunction "GND_137") (pintype "passive"))
      (node (ref "MO502") (pin "138") (pinfunction "GND_138") (pintype "passive"))
      (node (ref "MO502") (pin "144") (pinfunction "GND_144") (pintype "passive"))
      (node (ref "MO502") (pin "150") (pinfunction "GND_150") (pintype "passive"))
      (node (ref "MO502") (pin "155") (pinfunction "GND_155") (pintype "passive"))
      (node (ref "MO502") (pin "156") (pinfunction "GND_156") (pintype "passive"))
      (node (ref "MO502") (pin "161") (pinfunction "GND_161") (pintype "passive"))
      (node (ref "MO502") (pin "162") (pinfunction "GND_162") (pintype "passive"))
      (node (ref "MO502") (pin "167") (pinfunction "GND_167") (pintype "passive"))
      (node (ref "MO502") (pin "168") (pinfunction "GND_168") (pintype "passive"))
      (node (ref "MO502") (pin "173") (pinfunction "GND_173") (pintype "passive"))
      (node (ref "MO502") (pin "174") (pinfunction "GND_174") (pintype "passive"))
      (node (ref "MO502") (pin "179") (pinfunction "GND_179") (pintype "passive"))
      (node (ref "MO502") (pin "180") (pinfunction "GND_180") (pintype "passive"))
      (node (ref "MO502") (pin "185") (pinfunction "GND_185") (pintype "passive"))
      (node (ref "MO502") (pin "186") (pinfunction "GND_186") (pintype "passive"))
      (node (ref "MO502") (pin "191") (pinfunction "GND_191") (pintype "passive"))
      (node (ref "MO502") (pin "192") (pinfunction "GND_192") (pintype "passive"))
      (node (ref "MO502") (pin "197") (pinfunction "GND_197") (pintype "passive"))
      (node (ref "MO502") (pin "198") (pinfunction "GND_198") (pintype "passive"))
      (node (ref "MO503") (pin "GND") (pinfunction "GND_GND") (pintype "passive"))
      (node (ref "MO504") (pin "GND") (pinfunction "GND_GND") (pintype "passive"))
      (node (ref "MO505") (pin "GND") (pinfunction "GND_GND") (pintype "passive"))
      (node (ref "MO506") (pin "GND") (pinfunction "GND_GND") (pintype "passive"))
      (node (ref "R502") (pin "1") (pinfunction "1_1") (pintype "passive"))
      (node (ref "R506") (pin "1") (pinfunction "1_1") (pintype "passive"))
      (node (ref "R509") (pin "1") (pinfunction "1_1") (pintype "passive"))
      (node (ref "SW503") (pin "1") (pinfunction "1_1") (pintype "passive"))
      (node (ref "SW503") (pin "2") (pinfunction "2_2") (pintype "passive"))
      (node (ref "SW504") (pin "3") (pinfunction "3_3") (pintype "passive"))
      (node (ref "SW504") (pin "GND") (pinfunction "GND_GND") (pintype "passive"))
    )
    (net (code "65") (name "Net-(CO501-VDD)") (class "Default")
      (node (ref "C502") (pin "1") (pinfunction "1_1") (pintype "passive"))
      (node (ref "CO501") (pin "4") (pinfunction "VDD_4") (pintype "passive"))
      (node (ref "IC501") (pin "1") (pinfunction "Vout_1") (pintype "power_in"))
    )
    (net (code "66") (name "Net-(D501-PadA)") (class "Default")
      (node (ref "D501") (pin "A") (pinfunction "A_A") (pintype "passive"))
      (node (ref "R504") (pin "2") (pinfunction "2_2") (pintype "passive"))
    )
    (net (code "67") (name "Net-(D502-PadA)") (class "Default")
      (node (ref "D502") (pin "A") (pinfunction "A_A") (pintype "passive"))
      (node (ref "R510") (pin "1") (pinfunction "1_1") (pintype "passive"))
    )
    (net (code "68") (name "Net-(D504-PadA)") (class "Default")
      (node (ref "D504") (pin "A") (pinfunction "A_A") (pintype "passive"))
      (node (ref "R516") (pin "2") (pinfunction "2_2") (pintype "passive"))
    )
    (net (code "69") (name "Net-(D505-PadK)") (class "Default")
      (node (ref "D505") (pin "K") (pinfunction "K_K") (pintype "passive"))
      (node (ref "R515") (pin "2") (pinfunction "2_2") (pintype "passive"))
    )
    (net (code "70") (name "Net-(IC502-PWM)") (class "Default")
      (node (ref "IC502") (pin "5") (pinfunction "PWM_5") (pintype "passive"))
      (node (ref "J502") (pin "1") (pinfunction "PWM_1") (pintype "input"))
    )
    (net (code "71") (name "Net-(IC502-TACH)") (class "Default")
      (node (ref "IC502") (pin "6") (pinfunction "TACH_6") (pintype "passive"))
      (node (ref "J502") (pin "2") (pinfunction "Sense_2") (pintype "output"))
      (node (ref "R513") (pin "1") (pinfunction "1_1") (pintype "passive"))
    )
    (net (code "72") (name "Net-(IC504-Output)") (class "Default")
      (node (ref "IC504") (pin "4") (pinfunction "Output_4") (pintype "output"))
      (node (ref "R515") (pin "1") (pinfunction "1_1") (pintype "passive"))
    )
    (net (code "73") (name "Net-(MO501-PI_nLED_ACT)") (class "Default")
      (node (ref "D502") (pin "K") (pinfunction "K_K") (pintype "passive"))
      (node (ref "MO501") (pin "21") (pinfunction "PI_nLED_ACT_21") (pintype "passive"))
    )
    (net (code "74") (name "Net-(R503-Pad2)") (class "Default")
      (node (ref "R503") (pin "2") (pinfunction "2_2") (pintype "passive"))
      (node (ref "R517") (pin "1") (pinfunction "1_1") (pintype "passive"))
    )
    (net (code "75") (name "Net-(R507-Pad2)") (class "Default")
      (node (ref "R507") (pin "2") (pinfunction "2_2") (pintype "passive"))
      (node (ref "R518") (pin "1") (pinfunction "1_1") (pintype "passive"))
    )
    (net (code "76") (name "unconnected-(CO501-PadCD)") (class "Default")
      (node (ref "CO501") (pin "CD") (pinfunction "CD_CD") (pintype "passive"))
    )
    (net (code "77") (name "unconnected-(CO502-A2-Pad2)") (class "Default")
      (node (ref "CO502") (pin "2") (pinfunction "A2_2") (pintype "passive"))
    )
    (net (code "78") (name "unconnected-(CO502-A3-Pad3)") (class "Default")
      (node (ref "CO502") (pin "3") (pinfunction "A3_3") (pintype "passive"))
    )
    (net (code "79") (name "unconnected-(CO502-A8-Pad8)") (class "Default")
      (node (ref "CO502") (pin "8") (pinfunction "A8_8") (pintype "passive"))
    )
    (net (code "80") (name "unconnected-(CO502-A10-Pad10)") (class "Default")
      (node (ref "CO502") (pin "10") (pinfunction "A10_10") (pintype "passive"))
    )
    (net (code "81") (name "unconnected-(CO502-A11-Pad11)") (class "Default")
      (node (ref "CO502") (pin "11") (pinfunction "A11_11") (pintype "passive"))
    )
    (net (code "82") (name "unconnected-(CO502-B2-Pad22)") (class "Default")
      (node (ref "CO502") (pin "22") (pinfunction "B2_22") (pintype "passive"))
    )
    (net (code "83") (name "unconnected-(CO502-B3-Pad23)") (class "Default")
      (node (ref "CO502") (pin "23") (pinfunction "B3_23") (pintype "passive"))
    )
    (net (code "84") (name "unconnected-(CO502-B8-Pad28)") (class "Default")
      (node (ref "CO502") (pin "28") (pinfunction "B8_28") (pintype "passive"))
    )
    (net (code "85") (name "unconnected-(CO502-B10-Pad30)") (class "Default")
      (node (ref "CO502") (pin "30") (pinfunction "B10_30") (pintype "passive"))
    )
    (net (code "86") (name "unconnected-(CO502-B11-Pad31)") (class "Default")
      (node (ref "CO502") (pin "31") (pinfunction "B11_31") (pintype "passive"))
    )
    (net (code "87") (name "unconnected-(CO503-Pad14)") (class "Default")
      (node (ref "CO503") (pin "14") (pinfunction "14_14") (pintype "passive+no_connect"))
    )
    (net (code "88") (name "unconnected-(IC501-FLG-Pad3)") (class "Default")
      (node (ref "IC501") (pin "3") (pinfunction "FLG_3") (pintype "power_in"))
    )
    (net (code "89") (name "unconnected-(IC502-ALERT#-Pad8)") (class "Default")
      (node (ref "IC502") (pin "8") (pinfunction "ALERT#_8") (pintype "passive"))
    )
    (net (code "90") (name "unconnected-(IC502-CLK-Pad7)") (class "Default")
      (node (ref "IC502") (pin "7") (pinfunction "CLK_7") (pintype "passive"))
    )
    (net (code "91") (name "unconnected-(IC504-NC-Pad1)") (class "Default")
      (node (ref "IC504") (pin "1") (pinfunction "NC_1") (pintype "passive"))
    )
    (net (code "92") (name "unconnected-(MO501-AIN0-Pad96)") (class "Default")
      (node (ref "MO501") (pin "96") (pinfunction "AIN0_96") (pintype "passive"))
    )
    (net (code "93") (name "unconnected-(MO501-AIN1-Pad94)") (class "Default")
      (node (ref "MO501") (pin "94") (pinfunction "AIN1_94") (pintype "passive"))
    )
    (net (code "94") (name "unconnected-(MO501-CAMERA_GPIO-Pad97)") (class "Default")
      (node (ref "MO501") (pin "97") (pinfunction "CAMERA_GPIO_97") (pintype "passive"))
    )
    (net (code "95") (name "unconnected-(MO501-ETH_LEDG-Pad17)") (class "Default")
      (node (ref "MO501") (pin "17") (pinfunction "ETH_LEDG_17") (pintype "passive"))
    )
    (net (code "96") (name "unconnected-(MO501-ETH_LEDY-Pad15)") (class "Default")
      (node (ref "MO501") (pin "15") (pinfunction "ETH_LEDY_15") (pintype "passive"))
    )
    (net (code "97") (name "unconnected-(MO501-GPIO2-Pad58)") (class "Default")
      (node (ref "MO501") (pin "58") (pinfunction "GPIO2_58") (pintype "passive"))
    )
    (net (code "98") (name "unconnected-(MO501-GPIO3-Pad56)") (class "Default")
      (node (ref "MO501") (pin "56") (pinfunction "GPIO3_56") (pintype "passive"))
    )
    (net (code "99") (name "unconnected-(MO501-GPIO4-Pad54)") (class "Default")
      (node (ref "MO501") (pin "54") (pinfunction "GPIO4_54") (pintype "passive"))
    )
    (net (code "100") (name "unconnected-(MO501-GPIO5-Pad34)") (class "Default")
      (node (ref "MO501") (pin "34") (pinfunction "GPIO5_34") (pintype "passive"))
    )
    (net (code "101") (name "unconnected-(MO501-GPIO6-Pad30)") (class "Default")
      (node (ref "MO501") (pin "30") (pinfunction "GPIO6_30") (pintype "passive"))
    )
    (net (code "102") (name "unconnected-(MO501-GPIO7-Pad37)") (class "Default")
      (node (ref "MO501") (pin "37") (pinfunction "GPIO7_37") (pintype "passive"))
    )
    (net (code "103") (name "unconnected-(MO501-GPIO8-Pad39)") (class "Default")
      (node (ref "MO501") (pin "39") (pinfunction "GPIO8_39") (pintype "passive"))
    )
    (net (code "104") (name "unconnected-(MO501-GPIO9-Pad40)") (class "Default")
      (node (ref "MO501") (pin "40") (pinfunction "GPIO9_40") (pintype "passive"))
    )
    (net (code "105") (name "unconnected-(MO501-GPIO10-Pad44)") (class "Default")
      (node (ref "MO501") (pin "44") (pinfunction "GPIO10_44") (pintype "passive"))
    )
    (net (code "106") (name "unconnected-(MO501-GPIO11-Pad38)") (class "Default")
      (node (ref "MO501") (pin "38") (pinfunction "GPIO11_38") (pintype "passive"))
    )
    (net (code "107") (name "unconnected-(MO501-GPIO12-Pad31)") (class "Default")
      (node (ref "MO501") (pin "31") (pinfunction "GPIO12_31") (pintype "passive"))
    )
    (net (code "108") (name "unconnected-(MO501-GPIO13-Pad28)") (class "Default")
      (node (ref "MO501") (pin "28") (pinfunction "GPIO13_28") (pintype "passive"))
    )
    (net (code "109") (name "unconnected-(MO501-GPIO16-Pad29)") (class "Default")
      (node (ref "MO501") (pin "29") (pinfunction "GPIO16_29") (pintype "passive"))
    )
    (net (code "110") (name "unconnected-(MO501-GPIO17-Pad50)") (class "Default")
      (node (ref "MO501") (pin "50") (pinfunction "GPIO17_50") (pintype "passive"))
    )
    (net (code "111") (name "unconnected-(MO501-GPIO18-Pad49)") (class "Default")
      (node (ref "MO501") (pin "49") (pinfunction "GPIO18_49") (pintype "passive"))
    )
    (net (code "112") (name "unconnected-(MO501-GPIO19-Pad26)") (class "Default")
      (node (ref "MO501") (pin "26") (pinfunction "GPIO19_26") (pintype "passive"))
    )
    (net (code "113") (name "unconnected-(MO501-GPIO20-Pad27)") (class "Default")
      (node (ref "MO501") (pin "27") (pinfunction "GPIO20_27") (pintype "passive"))
    )
    (net (code "114") (name "unconnected-(MO501-GPIO21-Pad25)") (class "Default")
      (node (ref "MO501") (pin "25") (pinfunction "GPIO21_25") (pintype "passive"))
    )
    (net (code "115") (name "unconnected-(MO501-GPIO22-Pad46)") (class "Default")
      (node (ref "MO501") (pin "46") (pinfunction "GPIO22_46") (pintype "passive"))
    )
    (net (code "116") (name "unconnected-(MO501-GPIO23-Pad47)") (class "Default")
      (node (ref "MO501") (pin "47") (pinfunction "GPIO23_47") (pintype "passive"))
    )
    (net (code "117") (name "unconnected-(MO501-GPIO24-Pad45)") (class "Default")
      (node (ref "MO501") (pin "45") (pinfunction "GPIO24_45") (pintype "passive"))
    )
    (net (code "118") (name "unconnected-(MO501-GPIO25-Pad41)") (class "Default")
      (node (ref "MO501") (pin "41") (pinfunction "GPIO25_41") (pintype "passive"))
    )
    (net (code "119") (name "unconnected-(MO501-GPIO27-Pad48)") (class "Default")
      (node (ref "MO501") (pin "48") (pinfunction "GPIO27_48") (pintype "passive"))
    )
    (net (code "120") (name "unconnected-(MO501-ID_SC-Pad35)") (class "Default")
      (node (ref "MO501") (pin "35") (pinfunction "ID_SC_35") (pintype "passive"))
    )
    (net (code "121") (name "unconnected-(MO501-ID_SD-Pad36)") (class "Default")
      (node (ref "MO501") (pin "36") (pinfunction "ID_SD_36") (pintype "passive"))
    )
    (net (code "122") (name "unconnected-(MO501-NC-Pad19)") (class "Default")
      (node (ref "MO501") (pin "19") (pinfunction "NC_19") (pintype "passive"))
    )
    (net (code "123") (name "unconnected-(MO501-Reserved-Pad76)") (class "Default")
      (node (ref "MO501") (pin "76") (pinfunction "Reserved_76") (pintype "passive"))
    )
    (net (code "124") (name "unconnected-(MO501-SD_DAT4-Pad68)") (class "Default")
      (node (ref "MO501") (pin "68") (pinfunction "SD_DAT4_68") (pintype "passive"))
    )
    (net (code "125") (name "unconnected-(MO501-SD_DAT5-Pad64)") (class "Default")
      (node (ref "MO501") (pin "64") (pinfunction "SD_DAT5_64") (pintype "passive"))
    )
    (net (code "126") (name "unconnected-(MO501-SD_DAT6-Pad72)") (class "Default")
      (node (ref "MO501") (pin "72") (pinfunction "SD_DAT6_72") (pintype "passive"))
    )
    (net (code "127") (name "unconnected-(MO501-SD_DAT7-Pad70)") (class "Default")
      (node (ref "MO501") (pin "70") (pinfunction "SD_DAT7_70") (pintype "passive"))
    )
    (net (code "128") (name "unconnected-(MO501-SD_VDD_OVER-Pad73)") (class "Default")
      (node (ref "MO501") (pin "73") (pinfunction "SD_VDD_OVER_73") (pintype "passive"))
    )
    (net (code "129") (name "unconnected-(MO501-SYNC_IN(1.8V)-Pad16)") (class "Default")
      (node (ref "MO501") (pin "16") (pinfunction "SYNC_IN(1.8V)_16") (pintype "passive"))
    )
    (net (code "130") (name "unconnected-(MO501-SYNC_OUT(1.8V)-Pad18)") (class "Default")
      (node (ref "MO501") (pin "18") (pinfunction "SYNC_OUT(1.8V)_18") (pintype "passive"))
    )
    (net (code "131") (name "unconnected-(MO501-TRD0N-Pad10)") (class "Default")
      (node (ref "MO501") (pin "10") (pinfunction "TRD0N_10") (pintype "passive"))
    )
    (net (code "132") (name "unconnected-(MO501-TRD0P-Pad12)") (class "Default")
      (node (ref "MO501") (pin "12") (pinfunction "TRD0P_12") (pintype "passive"))
    )
    (net (code "133") (name "unconnected-(MO501-TRD1N-Pad6)") (class "Default")
      (node (ref "MO501") (pin "6") (pinfunction "TRD1N_6") (pintype "passive"))
    )
    (net (code "134") (name "unconnected-(MO501-TRD1P-Pad4)") (class "Default")
      (node (ref "MO501") (pin "4") (pinfunction "TRD1P_4") (pintype "passive"))
    )
    (net (code "135") (name "unconnected-(MO501-TRD2N-Pad9)") (class "Default")
      (node (ref "MO501") (pin "9") (pinfunction "TRD2N_9") (pintype "passive"))
    )
    (net (code "136") (name "unconnected-(MO501-TRD2P-Pad11)") (class "Default")
      (node (ref "MO501") (pin "11") (pinfunction "TRD2P_11") (pintype "passive"))
    )
    (net (code "137") (name "unconnected-(MO501-TRD3N-Pad5)") (class "Default")
      (node (ref "MO501") (pin "5") (pinfunction "TRD3N_5") (pintype "passive"))
    )
    (net (code "138") (name "unconnected-(MO501-TRD3P-Pad3)") (class "Default")
      (node (ref "MO501") (pin "3") (pinfunction "TRD3P_3") (pintype "passive"))
    )
    (net (code "139") (name "unconnected-(MO502-CAM0_C_N-Pad140)") (class "Default")
      (node (ref "MO502") (pin "140") (pinfunction "CAM0_C_N_140") (pintype "passive"))
    )
    (net (code "140") (name "unconnected-(MO502-CAM0_C_P-Pad142)") (class "Default")
      (node (ref "MO502") (pin "142") (pinfunction "CAM0_C_P_142") (pintype "passive"))
    )
    (net (code "141") (name "unconnected-(MO502-CAM0_D0_N-Pad128)") (class "Default")
      (node (ref "MO502") (pin "128") (pinfunction "CAM0_D0_N_128") (pintype "passive"))
    )
    (net (code "142") (name "unconnected-(MO502-CAM0_D0_P-Pad130)") (class "Default")
      (node (ref "MO502") (pin "130") (pinfunction "CAM0_D0_P_130") (pintype "passive"))
    )
    (net (code "143") (name "unconnected-(MO502-CAM0_D1_N-Pad134)") (class "Default")
      (node (ref "MO502") (pin "134") (pinfunction "CAM0_D1_N_134") (pintype "passive"))
    )
    (net (code "144") (name "unconnected-(MO502-CAM0_D1_P-Pad136)") (class "Default")
      (node (ref "MO502") (pin "136") (pinfunction "CAM0_D1_P_136") (pintype "passive"))
    )
    (net (code "145") (name "unconnected-(MO502-CAM1_C_N-Pad127)") (class "Default")
      (node (ref "MO502") (pin "127") (pinfunction "CAM1_C_N_127") (pintype "passive"))
    )
    (net (code "146") (name "unconnected-(MO502-CAM1_C_P-Pad129)") (class "Default")
      (node (ref "MO502") (pin "129") (pinfunction "CAM1_C_P_129") (pintype "passive"))
    )
    (net (code "147") (name "unconnected-(MO502-CAM1_D0_N-Pad115)") (class "Default")
      (node (ref "MO502") (pin "115") (pinfunction "CAM1_D0_N_115") (pintype "passive"))
    )
    (net (code "148") (name "unconnected-(MO502-CAM1_D0_P-Pad117)") (class "Default")
      (node (ref "MO502") (pin "117") (pinfunction "CAM1_D0_P_117") (pintype "passive"))
    )
    (net (code "149") (name "unconnected-(MO502-CAM1_D1_N-Pad121)") (class "Default")
      (node (ref "MO502") (pin "121") (pinfunction "CAM1_D1_N_121") (pintype "passive"))
    )
    (net (code "150") (name "unconnected-(MO502-CAM1_D1_P-Pad123)") (class "Default")
      (node (ref "MO502") (pin "123") (pinfunction "CAM1_D1_P_123") (pintype "passive"))
    )
    (net (code "151") (name "unconnected-(MO502-CAM1_D2_N-Pad133)") (class "Default")
      (node (ref "MO502") (pin "133") (pinfunction "CAM1_D2_N_133") (pintype "passive"))
    )
    (net (code "152") (name "unconnected-(MO502-CAM1_D2_P-Pad135)") (class "Default")
      (node (ref "MO502") (pin "135") (pinfunction "CAM1_D2_P_135") (pintype "passive"))
    )
    (net (code "153") (name "unconnected-(MO502-CAM1_D3_N-Pad139)") (class "Default")
      (node (ref "MO502") (pin "139") (pinfunction "CAM1_D3_N_139") (pintype "passive"))
    )
    (net (code "154") (name "unconnected-(MO502-CAM1_D3_P-Pad141)") (class "Default")
      (node (ref "MO502") (pin "141") (pinfunction "CAM1_D3_P_141") (pintype "passive"))
    )
    (net (code "155") (name "unconnected-(MO502-DSI0_C_N-Pad169)") (class "Default")
      (node (ref "MO502") (pin "169") (pinfunction "DSI0_C_N_169") (pintype "passive"))
    )
    (net (code "156") (name "unconnected-(MO502-DSI0_C_P-Pad171)") (class "Default")
      (node (ref "MO502") (pin "171") (pinfunction "DSI0_C_P_171") (pintype "passive"))
    )
    (net (code "157") (name "unconnected-(MO502-DSI0_D0_N-Pad157)") (class "Default")
      (node (ref "MO502") (pin "157") (pinfunction "DSI0_D0_N_157") (pintype "passive"))
    )
    (net (code "158") (name "unconnected-(MO502-DSI0_D0_P-Pad159)") (class "Default")
      (node (ref "MO502") (pin "159") (pinfunction "DSI0_D0_P_159") (pintype "passive"))
    )
    (net (code "159") (name "unconnected-(MO502-DSI0_D1_N-Pad163)") (class "Default")
      (node (ref "MO502") (pin "163") (pinfunction "DSI0_D1_N_163") (pintype "passive"))
    )
    (net (code "160") (name "unconnected-(MO502-DSI0_D1_P-Pad165)") (class "Default")
      (node (ref "MO502") (pin "165") (pinfunction "DSI0_D1_P_165") (pintype "passive"))
    )
    (net (code "161") (name "unconnected-(MO502-DSI1_C_N-Pad187)") (class "Default")
      (node (ref "MO502") (pin "187") (pinfunction "DSI1_C_N_187") (pintype "passive"))
    )
    (net (code "162") (name "unconnected-(MO502-DSI1_C_P-Pad189)") (class "Default")
      (node (ref "MO502") (pin "189") (pinfunction "DSI1_C_P_189") (pintype "passive"))
    )
    (net (code "163") (name "unconnected-(MO502-DSI1_D0_N-Pad175)") (class "Default")
      (node (ref "MO502") (pin "175") (pinfunction "DSI1_D0_N_175") (pintype "passive"))
    )
    (net (code "164") (name "unconnected-(MO502-DSI1_D0_P-Pad177)") (class "Default")
      (node (ref "MO502") (pin "177") (pinfunction "DSI1_D0_P_177") (pintype "passive"))
    )
    (net (code "165") (name "unconnected-(MO502-DSI1_D1_N-Pad181)") (class "Default")
      (node (ref "MO502") (pin "181") (pinfunction "DSI1_D1_N_181") (pintype "passive"))
    )
    (net (code "166") (name "unconnected-(MO502-DSI1_D1_P-Pad183)") (class "Default")
      (node (ref "MO502") (pin "183") (pinfunction "DSI1_D1_P_183") (pintype "passive"))
    )
    (net (code "167") (name "unconnected-(MO502-DSI1_D2_N-Pad193)") (class "Default")
      (node (ref "MO502") (pin "193") (pinfunction "DSI1_D2_N_193") (pintype "passive"))
    )
    (net (code "168") (name "unconnected-(MO502-DSI1_D2_P-Pad195)") (class "Default")
      (node (ref "MO502") (pin "195") (pinfunction "DSI1_D2_P_195") (pintype "passive"))
    )
    (net (code "169") (name "unconnected-(MO502-DSI1_D3_N-Pad194)") (class "Default")
      (node (ref "MO502") (pin "194") (pinfunction "DSI1_D3_N_194") (pintype "passive"))
    )
    (net (code "170") (name "unconnected-(MO502-DSI1_D3_P-Pad196)") (class "Default")
      (node (ref "MO502") (pin "196") (pinfunction "DSI1_D3_P_196") (pintype "passive"))
    )
    (net (code "171") (name "unconnected-(MO502-HDMI1_CEC-Pad149)") (class "Default")
      (node (ref "MO502") (pin "149") (pinfunction "HDMI1_CEC_149") (pintype "passive"))
    )
    (net (code "172") (name "unconnected-(MO502-HDMI1_CLK_N-Pad166)") (class "Default")
      (node (ref "MO502") (pin "166") (pinfunction "HDMI1_CLK_N_166") (pintype "passive"))
    )
    (net (code "173") (name "unconnected-(MO502-HDMI1_CLK_P-Pad164)") (class "Default")
      (node (ref "MO502") (pin "164") (pinfunction "HDMI1_CLK_P_164") (pintype "passive"))
    )
    (net (code "174") (name "unconnected-(MO502-HDMI1_HOT-Pad143)") (class "Default")
      (node (ref "MO502") (pin "143") (pinfunction "HDMI1_HOT_143") (pintype "passive"))
    )
    (net (code "175") (name "unconnected-(MO502-HDMI1_SCL-Pad147)") (class "Default")
      (node (ref "MO502") (pin "147") (pinfunction "HDMI1_SCL_147") (pintype "passive"))
    )
    (net (code "176") (name "unconnected-(MO502-HDMI1_SDA-Pad145)") (class "Default")
      (node (ref "MO502") (pin "145") (pinfunction "HDMI1_SDA_145") (pintype "passive"))
    )
    (net (code "177") (name "unconnected-(MO502-HDMI1_TX0_N-Pad160)") (class "Default")
      (node (ref "MO502") (pin "160") (pinfunction "HDMI1_TX0_N_160") (pintype "passive"))
    )
    (net (code "178") (name "unconnected-(MO502-HDMI1_TX0_P-Pad158)") (class "Default")
      (node (ref "MO502") (pin "158") (pinfunction "HDMI1_TX0_P_158") (pintype "passive"))
    )
    (net (code "179") (name "unconnected-(MO502-HDMI1_TX1_N-Pad154)") (class "Default")
      (node (ref "MO502") (pin "154") (pinfunction "HDMI1_TX1_N_154") (pintype "passive"))
    )
    (net (code "180") (name "unconnected-(MO502-HDMI1_TX1_P-Pad152)") (class "Default")
      (node (ref "MO502") (pin "152") (pinfunction "HDMI1_TX1_P_152") (pintype "passive"))
    )
    (net (code "181") (name "unconnected-(MO502-HDMI1_TX2_N-Pad148)") (class "Default")
      (node (ref "MO502") (pin "148") (pinfunction "HDMI1_TX2_N_148") (pintype "passive"))
    )
    (net (code "182") (name "unconnected-(MO502-HDMI1_TX2_P-Pad146)") (class "Default")
      (node (ref "MO502") (pin "146") (pinfunction "HDMI1_TX2_P_146") (pintype "passive"))
    )
    (net (code "183") (name "unconnected-(MO502-Reserved-Pad104)") (class "Default")
      (node (ref "MO502") (pin "104") (pinfunction "Reserved_104") (pintype "passive"))
    )
    (net (code "184") (name "unconnected-(MO502-Reserved-Pad106)") (class "Default")
      (node (ref "MO502") (pin "106") (pinfunction "Reserved_106") (pintype "passive"))
    )
    (net (code "185") (name "unconnected-(MO502-VDAC_COMP-Pad111)") (class "Default")
      (node (ref "MO502") (pin "111") (pinfunction "VDAC_COMP_111") (pintype "passive"))
    )
    (net (code "186") (name "unconnected-(SW504-Pad1)") (class "Default")
      (node (ref "SW504") (pin "1") (pinfunction "1_1") (pintype "passive"))
    )
  )
)
